# ZeroBug_MK2_REV1.net
KiCad netlist of a schematic drawn in EAGLE
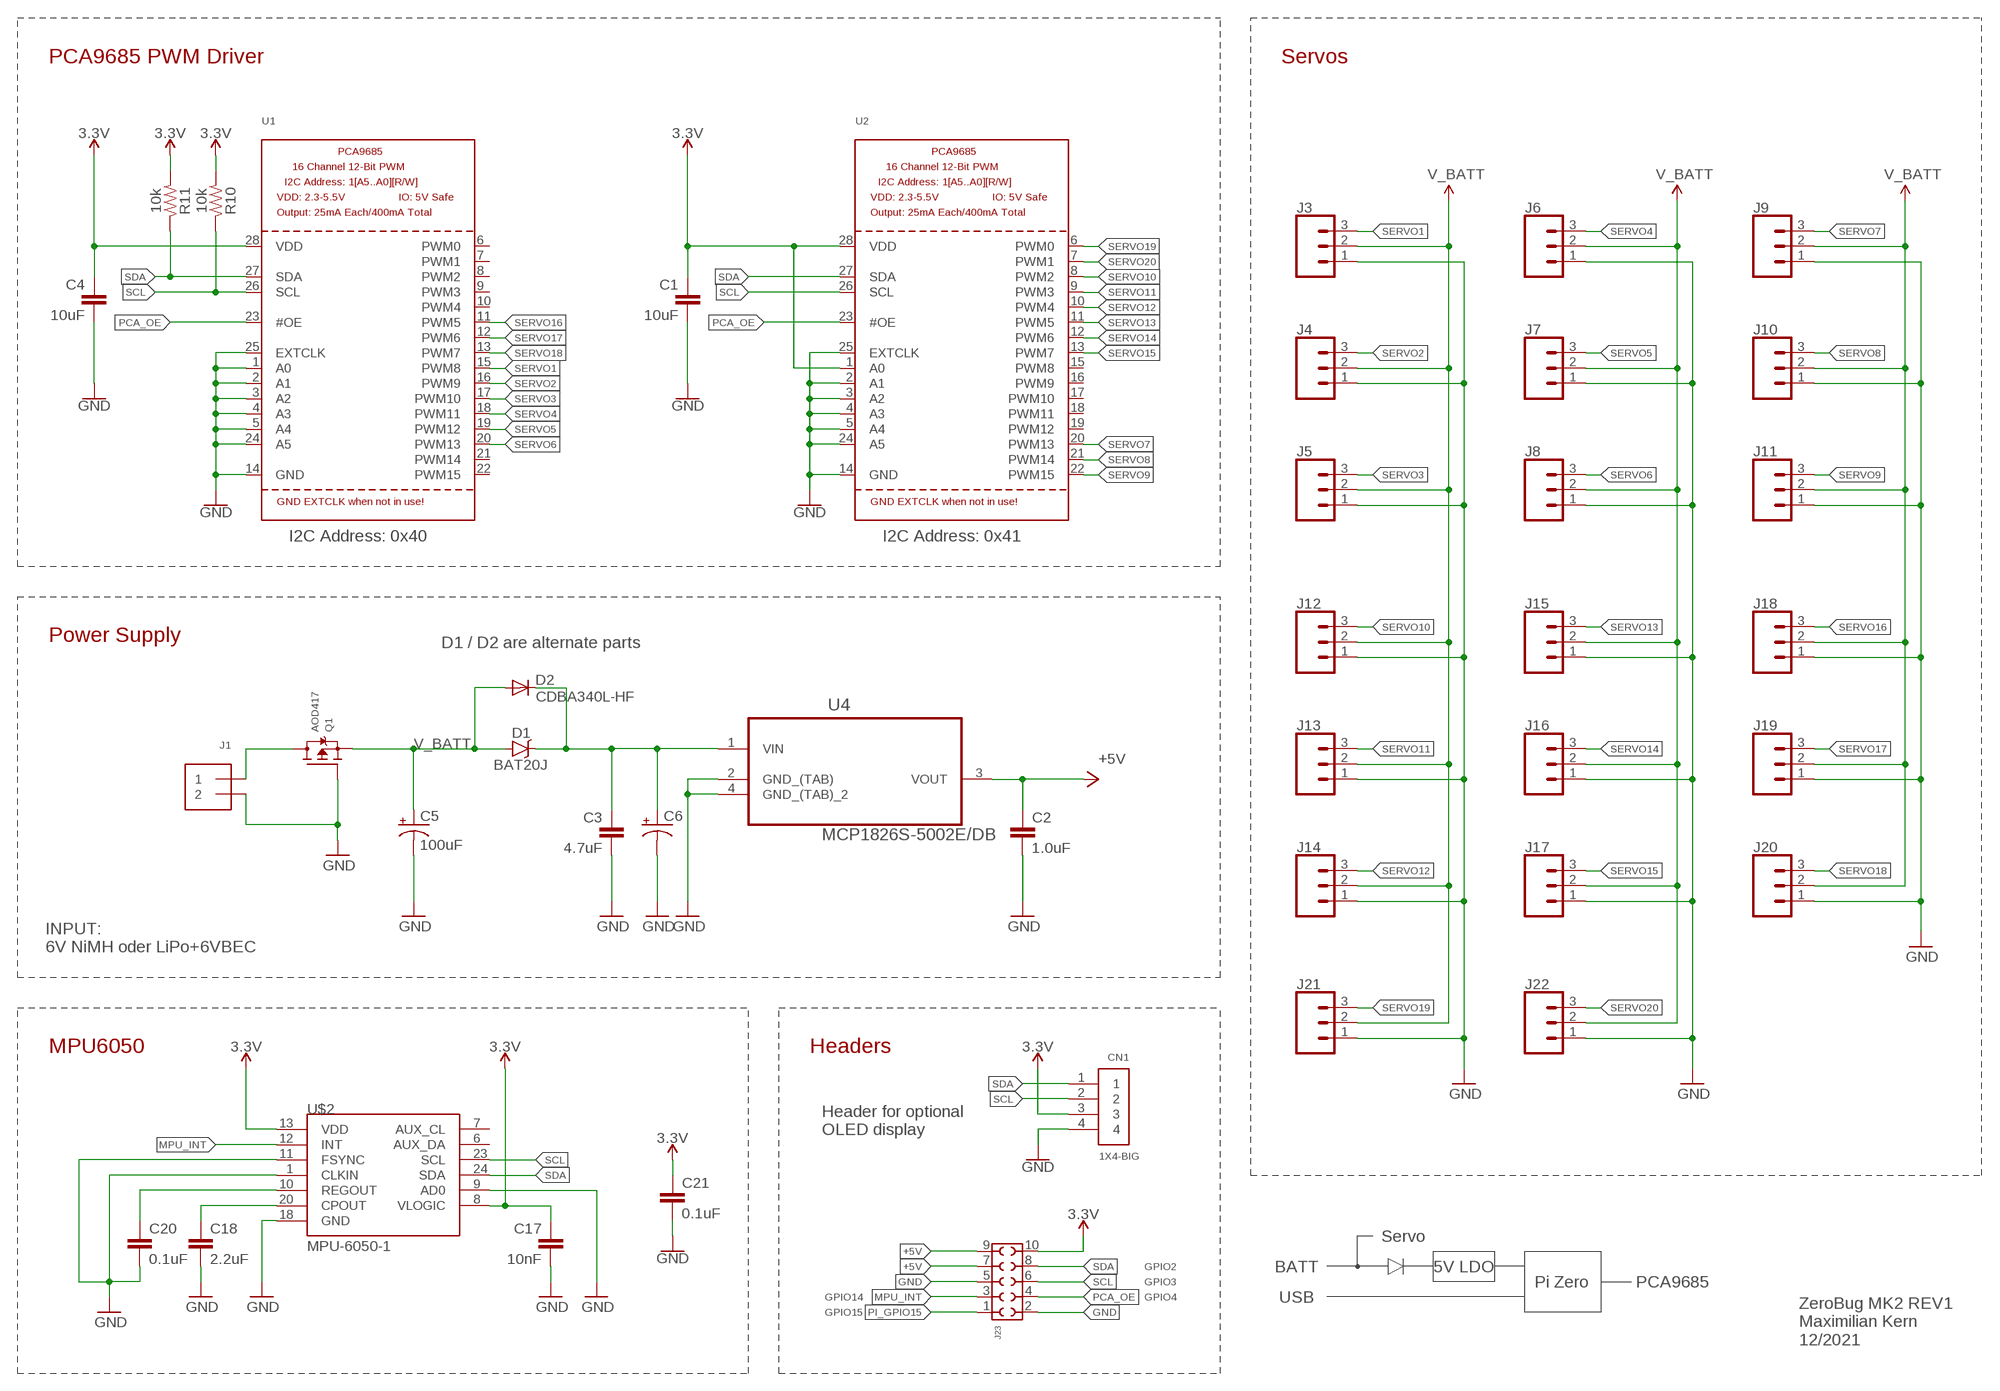
[diagram p0: schematic, sheet 1]

(export (version "E")
  (design (tool "Eeschema 10.0.6"))
  (components
    (comp (ref "C1")
      (value "10uF")
      (footprint "eagle-import:0805")
      (libsource (lib "eagle-import") (part "1.0UF-0805-25V-(+80/-20%)"))
    )
    (comp (ref "C2")
      (value "1.0uF")
      (footprint "eagle-import:0805")
      (libsource (lib "eagle-import") (part "1.0UF-0805-25V-(+80/-20%)"))
    )
    (comp (ref "C3")
      (value "4.7uF")
      (footprint "eagle-import:0805")
      (libsource (lib "eagle-import") (part "1.0UF-0805-25V-(+80/-20%)"))
    )
    (comp (ref "C4")
      (value "10uF")
      (footprint "eagle-import:0805")
      (libsource (lib "eagle-import") (part "1.0UF-0805-25V-(+80/-20%)"))
    )
    (comp (ref "C5")
      (value "100uF")
      (footprint "eagle-import:PANASONIC_D")
      (libsource (lib "eagle-import") (part "100UF-POLAR-25V-20%(ELEC)"))
    )
    (comp (ref "C6")
      (value "CPOL-USE5-10.5")
      (footprint "eagle-import:E5-10,5")
      (libsource (lib "eagle-import") (part "CPOL-USE5-10.5"))
    )
    (comp (ref "C17")
      (value "10nF")
      (footprint "eagle-import:0603")
      (libsource (lib "eagle-import") (part "47PF-0603-50V-5%"))
    )
    (comp (ref "C18")
      (value "2.2uF")
      (footprint "eagle-import:0805")
      (libsource (lib "eagle-import") (part "1.0UF-0805-25V-(+80/-20%)"))
    )
    (comp (ref "C20")
      (value "0.1uF")
      (footprint "eagle-import:0603")
      (libsource (lib "eagle-import") (part "0.1UF-0603-25V-(+80/-20%)"))
    )
    (comp (ref "C21")
      (value "0.1uF")
      (footprint "eagle-import:0603")
      (libsource (lib "eagle-import") (part "0.1UF-0603-25V-(+80/-20%)"))
    )
    (comp (ref "CN1")
      (value "1X4-BIG")
      (footprint "eagle-import:1X04-BIG")
      (libsource (lib "eagle-import") (part "1X4-BIG"))
    )
    (comp (ref "D1")
      (value "BAT20J")
      (footprint "eagle-import:SOD-323")
      (libsource (lib "eagle-import") (part "DIODE-SCHOTTKY-BAT20J"))
    )
    (comp (ref "D2")
      (value "CDBA340L-HF")
      (footprint "eagle-import:DO-214AC")
      (libsource (lib "eagle-import") (part "DIODE-DO-214AC"))
    )
    (comp (ref "J1")
      (value "TERMBLOCK_1X2")
      (footprint "eagle-import:TERMBLOCK_1X2-3.5MM")
      (libsource (lib "eagle-import") (part "TERMBLOCK_1X2"))
    )
    (comp (ref "J3")
      (value "CONN_03")
      (footprint "eagle-import:1X03")
      (libsource (lib "eagle-import") (part "CONN_03"))
    )
    (comp (ref "J4")
      (value "CONN_03")
      (footprint "eagle-import:1X03")
      (libsource (lib "eagle-import") (part "CONN_03"))
    )
    (comp (ref "J5")
      (value "CONN_03")
      (footprint "eagle-import:1X03")
      (libsource (lib "eagle-import") (part "CONN_03"))
    )
    (comp (ref "J6")
      (value "CONN_03")
      (footprint "eagle-import:1X03")
      (libsource (lib "eagle-import") (part "CONN_03"))
    )
    (comp (ref "J7")
      (value "CONN_03")
      (footprint "eagle-import:1X03")
      (libsource (lib "eagle-import") (part "CONN_03"))
    )
    (comp (ref "J8")
      (value "CONN_03")
      (footprint "eagle-import:1X03")
      (libsource (lib "eagle-import") (part "CONN_03"))
    )
    (comp (ref "J9")
      (value "CONN_03")
      (footprint "eagle-import:1X03")
      (libsource (lib "eagle-import") (part "CONN_03"))
    )
    (comp (ref "J10")
      (value "CONN_03")
      (footprint "eagle-import:1X03")
      (libsource (lib "eagle-import") (part "CONN_03"))
    )
    (comp (ref "J11")
      (value "CONN_03")
      (footprint "eagle-import:1X03")
      (libsource (lib "eagle-import") (part "CONN_03"))
    )
    (comp (ref "J12")
      (value "CONN_03")
      (footprint "eagle-import:1X03")
      (libsource (lib "eagle-import") (part "CONN_03"))
    )
    (comp (ref "J13")
      (value "CONN_03")
      (footprint "eagle-import:1X03")
      (libsource (lib "eagle-import") (part "CONN_03"))
    )
    (comp (ref "J14")
      (value "CONN_03")
      (footprint "eagle-import:1X03")
      (libsource (lib "eagle-import") (part "CONN_03"))
    )
    (comp (ref "J15")
      (value "CONN_03")
      (footprint "eagle-import:1X03")
      (libsource (lib "eagle-import") (part "CONN_03"))
    )
    (comp (ref "J16")
      (value "CONN_03")
      (footprint "eagle-import:1X03")
      (libsource (lib "eagle-import") (part "CONN_03"))
    )
    (comp (ref "J17")
      (value "CONN_03")
      (footprint "eagle-import:1X03")
      (libsource (lib "eagle-import") (part "CONN_03"))
    )
    (comp (ref "J18")
      (value "CONN_03")
      (footprint "eagle-import:1X03")
      (libsource (lib "eagle-import") (part "CONN_03"))
    )
    (comp (ref "J19")
      (value "CONN_03")
      (footprint "eagle-import:1X03")
      (libsource (lib "eagle-import") (part "CONN_03"))
    )
    (comp (ref "J20")
      (value "CONN_03")
      (footprint "eagle-import:1X03")
      (libsource (lib "eagle-import") (part "CONN_03"))
    )
    (comp (ref "J21")
      (value "CONN_03")
      (footprint "eagle-import:1X03")
      (libsource (lib "eagle-import") (part "CONN_03"))
    )
    (comp (ref "J22")
      (value "CONN_03")
      (footprint "eagle-import:1X03")
      (libsource (lib "eagle-import") (part "CONN_03"))
    )
    (comp (ref "J23")
      (value "6103XX21821_61031021821")
      (footprint "eagle-import:61031021821")
      (libsource (lib "eagle-import") (part "6103XX21821_61031021821"))
    )
    (comp (ref "Q1")
      (value "AOD417")
      (footprint "eagle-import:TO252")
      (libsource (lib "eagle-import") (part "MOSFET-PTO252"))
    )
    (comp (ref "R10")
      (value "10k")
      (footprint "eagle-import:0603")
      (libsource (lib "eagle-import") (part "10KOHM-0603-1/10W-1%"))
    )
    (comp (ref "R11")
      (value "10k")
      (footprint "eagle-import:0603")
      (libsource (lib "eagle-import") (part "10KOHM-0603-1/10W-1%"))
    )
    (comp (ref "U$2")
      (value "MPU-6050-1")
      (footprint "eagle-import:QFN-24-4MM2")
      (libsource (lib "eagle-import") (part "MPU-6050-1"))
    )
    (comp (ref "U1")
      (value "PCA9685")
      (footprint "eagle-import:TSSOP28")
      (libsource (lib "eagle-import") (part "PCA9685"))
    )
    (comp (ref "U2")
      (value "PCA9685")
      (footprint "eagle-import:TSSOP28")
      (libsource (lib "eagle-import") (part "PCA9685"))
    )
    (comp (ref "U4")
      (value "MCP1826S-5002E/DB")
      (footprint "eagle-import:SOT230P700X180-4N")
      (fields (field (name "MPN") "MCP1825S-5002E/DB"))
      (libsource (lib "eagle-import") (part "MCP1825S-5002E/DB"))
    )
  )
  (nets
    (net (code "1") (name "+5V") (class "Default")
      (node (ref "C2") (pin "1") (pinfunction "1_1") (pintype "passive"))
      (node (ref "J23") (pin "7") (pinfunction "7_7") (pintype "passive"))
      (node (ref "J23") (pin "9") (pinfunction "9_9") (pintype "passive"))
      (node (ref "U4") (pin "3") (pinfunction "VOUT_3") (pintype "output"))
    )
    (net (code "2") (name "3.3V") (class "Default")
      (node (ref "C1") (pin "1") (pinfunction "1_1") (pintype "passive"))
      (node (ref "C17") (pin "1") (pinfunction "1_1") (pintype "passive"))
      (node (ref "C21") (pin "1") (pinfunction "1_1") (pintype "passive"))
      (node (ref "C4") (pin "1") (pinfunction "1_1") (pintype "passive"))
      (node (ref "CN1") (pin "3") (pinfunction "3_3") (pintype "bidirectional"))
      (node (ref "J23") (pin "10") (pinfunction "10_10") (pintype "passive"))
      (node (ref "R10") (pin "2") (pinfunction "2_2") (pintype "passive"))
      (node (ref "R11") (pin "2") (pinfunction "2_2") (pintype "passive"))
      (node (ref "U$2") (pin "13") (pinfunction "VDD_13") (pintype "bidirectional"))
      (node (ref "U$2") (pin "8") (pinfunction "VLOGIC_8") (pintype "bidirectional"))
      (node (ref "U1") (pin "28") (pinfunction "VDD_28") (pintype "power_in"))
      (node (ref "U2") (pin "1") (pinfunction "A0_1") (pintype "bidirectional"))
      (node (ref "U2") (pin "28") (pinfunction "VDD_28") (pintype "power_in"))
    )
    (net (code "3") (name "GND") (class "Default")
      (node (ref "C1") (pin "2") (pinfunction "2_2") (pintype "passive"))
      (node (ref "C17") (pin "2") (pinfunction "2_2") (pintype "passive"))
      (node (ref "C18") (pin "2") (pinfunction "2_2") (pintype "passive"))
      (node (ref "C2") (pin "2") (pinfunction "2_2") (pintype "passive"))
      (node (ref "C20") (pin "2") (pinfunction "2_2") (pintype "passive"))
      (node (ref "C21") (pin "2") (pinfunction "2_2") (pintype "passive"))
      (node (ref "C3") (pin "2") (pinfunction "2_2") (pintype "passive"))
      (node (ref "C4") (pin "2") (pinfunction "2_2") (pintype "passive"))
      (node (ref "C5") (pin "-") (pinfunction "-_-") (pintype "passive"))
      (node (ref "C6") (pin "-") (pinfunction "-_-") (pintype "passive"))
      (node (ref "CN1") (pin "4") (pinfunction "4_4") (pintype "bidirectional"))
      (node (ref "J1") (pin "2") (pinfunction "2_2") (pintype "passive"))
      (node (ref "J10") (pin "1") (pinfunction "1_1") (pintype "passive"))
      (node (ref "J11") (pin "1") (pinfunction "1_1") (pintype "passive"))
      (node (ref "J12") (pin "1") (pinfunction "1_1") (pintype "passive"))
      (node (ref "J13") (pin "1") (pinfunction "1_1") (pintype "passive"))
      (node (ref "J14") (pin "1") (pinfunction "1_1") (pintype "passive"))
      (node (ref "J15") (pin "1") (pinfunction "1_1") (pintype "passive"))
      (node (ref "J16") (pin "1") (pinfunction "1_1") (pintype "passive"))
      (node (ref "J17") (pin "1") (pinfunction "1_1") (pintype "passive"))
      (node (ref "J18") (pin "1") (pinfunction "1_1") (pintype "passive"))
      (node (ref "J19") (pin "1") (pinfunction "1_1") (pintype "passive"))
      (node (ref "J20") (pin "1") (pinfunction "1_1") (pintype "passive"))
      (node (ref "J21") (pin "1") (pinfunction "1_1") (pintype "passive"))
      (node (ref "J22") (pin "1") (pinfunction "1_1") (pintype "passive"))
      (node (ref "J23") (pin "2") (pinfunction "2_2") (pintype "passive"))
      (node (ref "J23") (pin "5") (pinfunction "5_5") (pintype "passive"))
      (node (ref "J3") (pin "1") (pinfunction "1_1") (pintype "passive"))
      (node (ref "J4") (pin "1") (pinfunction "1_1") (pintype "passive"))
      (node (ref "J5") (pin "1") (pinfunction "1_1") (pintype "passive"))
      (node (ref "J6") (pin "1") (pinfunction "1_1") (pintype "passive"))
      (node (ref "J7") (pin "1") (pinfunction "1_1") (pintype "passive"))
      (node (ref "J8") (pin "1") (pinfunction "1_1") (pintype "passive"))
      (node (ref "J9") (pin "1") (pinfunction "1_1") (pintype "passive"))
      (node (ref "Q1") (pin "1") (pinfunction "G_1") (pintype "passive"))
      (node (ref "U$2") (pin "1") (pinfunction "CLKIN_1") (pintype "bidirectional"))
      (node (ref "U$2") (pin "11") (pinfunction "FSYNC_11") (pintype "bidirectional"))
      (node (ref "U$2") (pin "18") (pinfunction "GND_18") (pintype "bidirectional"))
      (node (ref "U$2") (pin "9") (pinfunction "AD0_9") (pintype "bidirectional"))
      (node (ref "U1") (pin "1") (pinfunction "A0_1") (pintype "bidirectional"))
      (node (ref "U1") (pin "14") (pinfunction "GND_14") (pintype "power_in"))
      (node (ref "U1") (pin "2") (pinfunction "A1_2") (pintype "bidirectional"))
      (node (ref "U1") (pin "24") (pinfunction "A5_24") (pintype "bidirectional"))
      (node (ref "U1") (pin "25") (pinfunction "EXTCLK_25") (pintype "input"))
      (node (ref "U1") (pin "3") (pinfunction "A2_3") (pintype "bidirectional"))
      (node (ref "U1") (pin "4") (pinfunction "A3_4") (pintype "bidirectional"))
      (node (ref "U1") (pin "5") (pinfunction "A4_5") (pintype "bidirectional"))
      (node (ref "U2") (pin "14") (pinfunction "GND_14") (pintype "power_in"))
      (node (ref "U2") (pin "2") (pinfunction "A1_2") (pintype "bidirectional"))
      (node (ref "U2") (pin "24") (pinfunction "A5_24") (pintype "bidirectional"))
      (node (ref "U2") (pin "25") (pinfunction "EXTCLK_25") (pintype "input"))
      (node (ref "U2") (pin "3") (pinfunction "A2_3") (pintype "bidirectional"))
      (node (ref "U2") (pin "4") (pinfunction "A3_4") (pintype "bidirectional"))
      (node (ref "U2") (pin "5") (pinfunction "A4_5") (pintype "bidirectional"))
      (node (ref "U4") (pin "2") (pinfunction "GND_(TAB)_2") (pintype "passive"))
      (node (ref "U4") (pin "4") (pinfunction "GND_(TAB)_2_4") (pintype "passive"))
    )
    (net (code "4") (name "MPU_INT") (class "Default")
      (node (ref "J23") (pin "3") (pinfunction "3_3") (pintype "passive"))
      (node (ref "U$2") (pin "12") (pinfunction "INT_12") (pintype "bidirectional"))
    )
    (net (code "5") (name "Net-(Q1-D)") (class "Default")
      (node (ref "J1") (pin "1") (pinfunction "1_1") (pintype "passive"))
      (node (ref "Q1") (pin "3") (pinfunction "D_3") (pintype "passive"))
    )
    (net (code "6") (name "Net-(U$2-CPOUT)") (class "Default")
      (node (ref "C18") (pin "1") (pinfunction "1_1") (pintype "passive"))
      (node (ref "U$2") (pin "20") (pinfunction "CPOUT_20") (pintype "bidirectional"))
    )
    (net (code "7") (name "Net-(U$2-REGOUT)") (class "Default")
      (node (ref "C20") (pin "1") (pinfunction "1_1") (pintype "passive"))
      (node (ref "U$2") (pin "10") (pinfunction "REGOUT_10") (pintype "bidirectional"))
    )
    (net (code "8") (name "Net-(U4-VIN)") (class "Default")
      (node (ref "C3") (pin "1") (pinfunction "1_1") (pintype "passive"))
      (node (ref "C6") (pin "+") (pinfunction "+_+") (pintype "passive"))
      (node (ref "D1") (pin "C") (pinfunction "C_C") (pintype "passive"))
      (node (ref "D2") (pin "C") (pinfunction "C_C") (pintype "passive"))
      (node (ref "U4") (pin "1") (pinfunction "VIN_1") (pintype "input"))
    )
    (net (code "9") (name "PCA_OE") (class "Default")
      (node (ref "J23") (pin "4") (pinfunction "4_4") (pintype "passive"))
      (node (ref "U1") (pin "23") (pinfunction "#OE_23") (pintype "input"))
      (node (ref "U2") (pin "23") (pinfunction "#OE_23") (pintype "input"))
    )
    (net (code "10") (name "PI_GPIO15") (class "Default")
      (node (ref "J23") (pin "1") (pinfunction "1_1") (pintype "passive"))
    )
    (net (code "11") (name "SCL") (class "Default")
      (node (ref "CN1") (pin "2") (pinfunction "2_2") (pintype "bidirectional"))
      (node (ref "J23") (pin "6") (pinfunction "6_6") (pintype "passive"))
      (node (ref "R10") (pin "1") (pinfunction "1_1") (pintype "passive"))
      (node (ref "U$2") (pin "23") (pinfunction "SCL_23") (pintype "bidirectional"))
      (node (ref "U1") (pin "26") (pinfunction "SCL_26") (pintype "bidirectional"))
      (node (ref "U2") (pin "26") (pinfunction "SCL_26") (pintype "bidirectional"))
    )
    (net (code "12") (name "SDA") (class "Default")
      (node (ref "CN1") (pin "1") (pinfunction "1_1") (pintype "bidirectional"))
      (node (ref "J23") (pin "8") (pinfunction "8_8") (pintype "passive"))
      (node (ref "R11") (pin "1") (pinfunction "1_1") (pintype "passive"))
      (node (ref "U$2") (pin "24") (pinfunction "SDA_24") (pintype "bidirectional"))
      (node (ref "U1") (pin "27") (pinfunction "SDA_27") (pintype "bidirectional"))
      (node (ref "U2") (pin "27") (pinfunction "SDA_27") (pintype "bidirectional"))
    )
    (net (code "13") (name "SERVO1") (class "Default")
      (node (ref "J3") (pin "3") (pinfunction "3_3") (pintype "passive"))
      (node (ref "U1") (pin "15") (pinfunction "PWM8_15") (pintype "output"))
    )
    (net (code "14") (name "SERVO2") (class "Default")
      (node (ref "J4") (pin "3") (pinfunction "3_3") (pintype "passive"))
      (node (ref "U1") (pin "16") (pinfunction "PWM9_16") (pintype "output"))
    )
    (net (code "15") (name "SERVO3") (class "Default")
      (node (ref "J5") (pin "3") (pinfunction "3_3") (pintype "passive"))
      (node (ref "U1") (pin "17") (pinfunction "PWM10_17") (pintype "output"))
    )
    (net (code "16") (name "SERVO4") (class "Default")
      (node (ref "J6") (pin "3") (pinfunction "3_3") (pintype "passive"))
      (node (ref "U1") (pin "18") (pinfunction "PWM11_18") (pintype "output"))
    )
    (net (code "17") (name "SERVO5") (class "Default")
      (node (ref "J7") (pin "3") (pinfunction "3_3") (pintype "passive"))
      (node (ref "U1") (pin "19") (pinfunction "PWM12_19") (pintype "output"))
    )
    (net (code "18") (name "SERVO6") (class "Default")
      (node (ref "J8") (pin "3") (pinfunction "3_3") (pintype "passive"))
      (node (ref "U1") (pin "20") (pinfunction "PWM13_20") (pintype "output"))
    )
    (net (code "19") (name "SERVO7") (class "Default")
      (node (ref "J9") (pin "3") (pinfunction "3_3") (pintype "passive"))
      (node (ref "U2") (pin "20") (pinfunction "PWM13_20") (pintype "output"))
    )
    (net (code "20") (name "SERVO8") (class "Default")
      (node (ref "J10") (pin "3") (pinfunction "3_3") (pintype "passive"))
      (node (ref "U2") (pin "21") (pinfunction "PWM14_21") (pintype "output"))
    )
    (net (code "21") (name "SERVO9") (class "Default")
      (node (ref "J11") (pin "3") (pinfunction "3_3") (pintype "passive"))
      (node (ref "U2") (pin "22") (pinfunction "PWM15_22") (pintype "output"))
    )
    (net (code "22") (name "SERVO10") (class "Default")
      (node (ref "J12") (pin "3") (pinfunction "3_3") (pintype "passive"))
      (node (ref "U2") (pin "8") (pinfunction "PWM2_8") (pintype "output"))
    )
    (net (code "23") (name "SERVO11") (class "Default")
      (node (ref "J13") (pin "3") (pinfunction "3_3") (pintype "passive"))
      (node (ref "U2") (pin "9") (pinfunction "PWM3_9") (pintype "output"))
    )
    (net (code "24") (name "SERVO12") (class "Default")
      (node (ref "J14") (pin "3") (pinfunction "3_3") (pintype "passive"))
      (node (ref "U2") (pin "10") (pinfunction "PWM4_10") (pintype "output"))
    )
    (net (code "25") (name "SERVO13") (class "Default")
      (node (ref "J15") (pin "3") (pinfunction "3_3") (pintype "passive"))
      (node (ref "U2") (pin "11") (pinfunction "PWM5_11") (pintype "output"))
    )
    (net (code "26") (name "SERVO14") (class "Default")
      (node (ref "J16") (pin "3") (pinfunction "3_3") (pintype "passive"))
      (node (ref "U2") (pin "12") (pinfunction "PWM6_12") (pintype "output"))
    )
    (net (code "27") (name "SERVO15") (class "Default")
      (node (ref "J17") (pin "3") (pinfunction "3_3") (pintype "passive"))
      (node (ref "U2") (pin "13") (pinfunction "PWM7_13") (pintype "output"))
    )
    (net (code "28") (name "SERVO16") (class "Default")
      (node (ref "J18") (pin "3") (pinfunction "3_3") (pintype "passive"))
      (node (ref "U1") (pin "11") (pinfunction "PWM5_11") (pintype "output"))
    )
    (net (code "29") (name "SERVO17") (class "Default")
      (node (ref "J19") (pin "3") (pinfunction "3_3") (pintype "passive"))
      (node (ref "U1") (pin "12") (pinfunction "PWM6_12") (pintype "output"))
    )
    (net (code "30") (name "SERVO18") (class "Default")
      (node (ref "J20") (pin "3") (pinfunction "3_3") (pintype "passive"))
      (node (ref "U1") (pin "13") (pinfunction "PWM7_13") (pintype "output"))
    )
    (net (code "31") (name "SERVO19") (class "Default")
      (node (ref "J21") (pin "3") (pinfunction "3_3") (pintype "passive"))
      (node (ref "U2") (pin "6") (pinfunction "PWM0_6") (pintype "output"))
    )
    (net (code "32") (name "SERVO20") (class "Default")
      (node (ref "J22") (pin "3") (pinfunction "3_3") (pintype "passive"))
      (node (ref "U2") (pin "7") (pinfunction "PWM1_7") (pintype "output"))
    )
    (net (code "33") (name "V_BATT") (class "Default")
      (node (ref "C5") (pin "+") (pinfunction "+_+") (pintype "passive"))
      (node (ref "D1") (pin "A") (pinfunction "A_A") (pintype "passive"))
      (node (ref "D2") (pin "A") (pinfunction "A_A") (pintype "passive"))
      (node (ref "J10") (pin "2") (pinfunction "2_2") (pintype "passive"))
      (node (ref "J11") (pin "2") (pinfunction "2_2") (pintype "passive"))
      (node (ref "J12") (pin "2") (pinfunction "2_2") (pintype "passive"))
      (node (ref "J13") (pin "2") (pinfunction "2_2") (pintype "passive"))
      (node (ref "J14") (pin "2") (pinfunction "2_2") (pintype "passive"))
      (node (ref "J15") (pin "2") (pinfunction "2_2") (pintype "passive"))
      (node (ref "J16") (pin "2") (pinfunction "2_2") (pintype "passive"))
      (node (ref "J17") (pin "2") (pinfunction "2_2") (pintype "passive"))
      (node (ref "J18") (pin "2") (pinfunction "2_2") (pintype "passive"))
      (node (ref "J19") (pin "2") (pinfunction "2_2") (pintype "passive"))
      (node (ref "J20") (pin "2") (pinfunction "2_2") (pintype "passive"))
      (node (ref "J21") (pin "2") (pinfunction "2_2") (pintype "passive"))
      (node (ref "J22") (pin "2") (pinfunction "2_2") (pintype "passive"))
      (node (ref "J3") (pin "2") (pinfunction "2_2") (pintype "passive"))
      (node (ref "J4") (pin "2") (pinfunction "2_2") (pintype "passive"))
      (node (ref "J5") (pin "2") (pinfunction "2_2") (pintype "passive"))
      (node (ref "J6") (pin "2") (pinfunction "2_2") (pintype "passive"))
      (node (ref "J7") (pin "2") (pinfunction "2_2") (pintype "passive"))
      (node (ref "J8") (pin "2") (pinfunction "2_2") (pintype "passive"))
      (node (ref "J9") (pin "2") (pinfunction "2_2") (pintype "passive"))
      (node (ref "Q1") (pin "2") (pinfunction "S_2") (pintype "passive"))
    )
    (net (code "34") (name "unconnected-(U$2-AUX_CL-Pad7)") (class "Default")
      (node (ref "U$2") (pin "7") (pinfunction "AUX_CL_7") (pintype "bidirectional"))
    )
    (net (code "35") (name "unconnected-(U$2-AUX_DA-Pad6)") (class "Default")
      (node (ref "U$2") (pin "6") (pinfunction "AUX_DA_6") (pintype "bidirectional"))
    )
    (net (code "36") (name "unconnected-(U1-PWM0-Pad6)") (class "Default")
      (node (ref "U1") (pin "6") (pinfunction "PWM0_6") (pintype "output"))
    )
    (net (code "37") (name "unconnected-(U1-PWM1-Pad7)") (class "Default")
      (node (ref "U1") (pin "7") (pinfunction "PWM1_7") (pintype "output"))
    )
    (net (code "38") (name "unconnected-(U1-PWM2-Pad8)") (class "Default")
      (node (ref "U1") (pin "8") (pinfunction "PWM2_8") (pintype "output"))
    )
    (net (code "39") (name "unconnected-(U1-PWM3-Pad9)") (class "Default")
      (node (ref "U1") (pin "9") (pinfunction "PWM3_9") (pintype "output"))
    )
    (net (code "40") (name "unconnected-(U1-PWM4-Pad10)") (class "Default")
      (node (ref "U1") (pin "10") (pinfunction "PWM4_10") (pintype "output"))
    )
    (net (code "41") (name "unconnected-(U1-PWM14-Pad21)") (class "Default")
      (node (ref "U1") (pin "21") (pinfunction "PWM14_21") (pintype "output"))
    )
    (net (code "42") (name "unconnected-(U1-PWM15-Pad22)") (class "Default")
      (node (ref "U1") (pin "22") (pinfunction "PWM15_22") (pintype "output"))
    )
    (net (code "43") (name "unconnected-(U2-PWM8-Pad15)") (class "Default")
      (node (ref "U2") (pin "15") (pinfunction "PWM8_15") (pintype "output"))
    )
    (net (code "44") (name "unconnected-(U2-PWM9-Pad16)") (class "Default")
      (node (ref "U2") (pin "16") (pinfunction "PWM9_16") (pintype "output"))
    )
    (net (code "45") (name "unconnected-(U2-PWM10-Pad17)") (class "Default")
      (node (ref "U2") (pin "17") (pinfunction "PWM10_17") (pintype "output"))
    )
    (net (code "46") (name "unconnected-(U2-PWM11-Pad18)") (class "Default")
      (node (ref "U2") (pin "18") (pinfunction "PWM11_18") (pintype "output"))
    )
    (net (code "47") (name "unconnected-(U2-PWM12-Pad19)") (class "Default")
      (node (ref "U2") (pin "19") (pinfunction "PWM12_19") (pintype "output"))
    )
  )
)
